# PortExpanderXRA1207.net
KiCad netlist of a schematic drawn in EAGLE
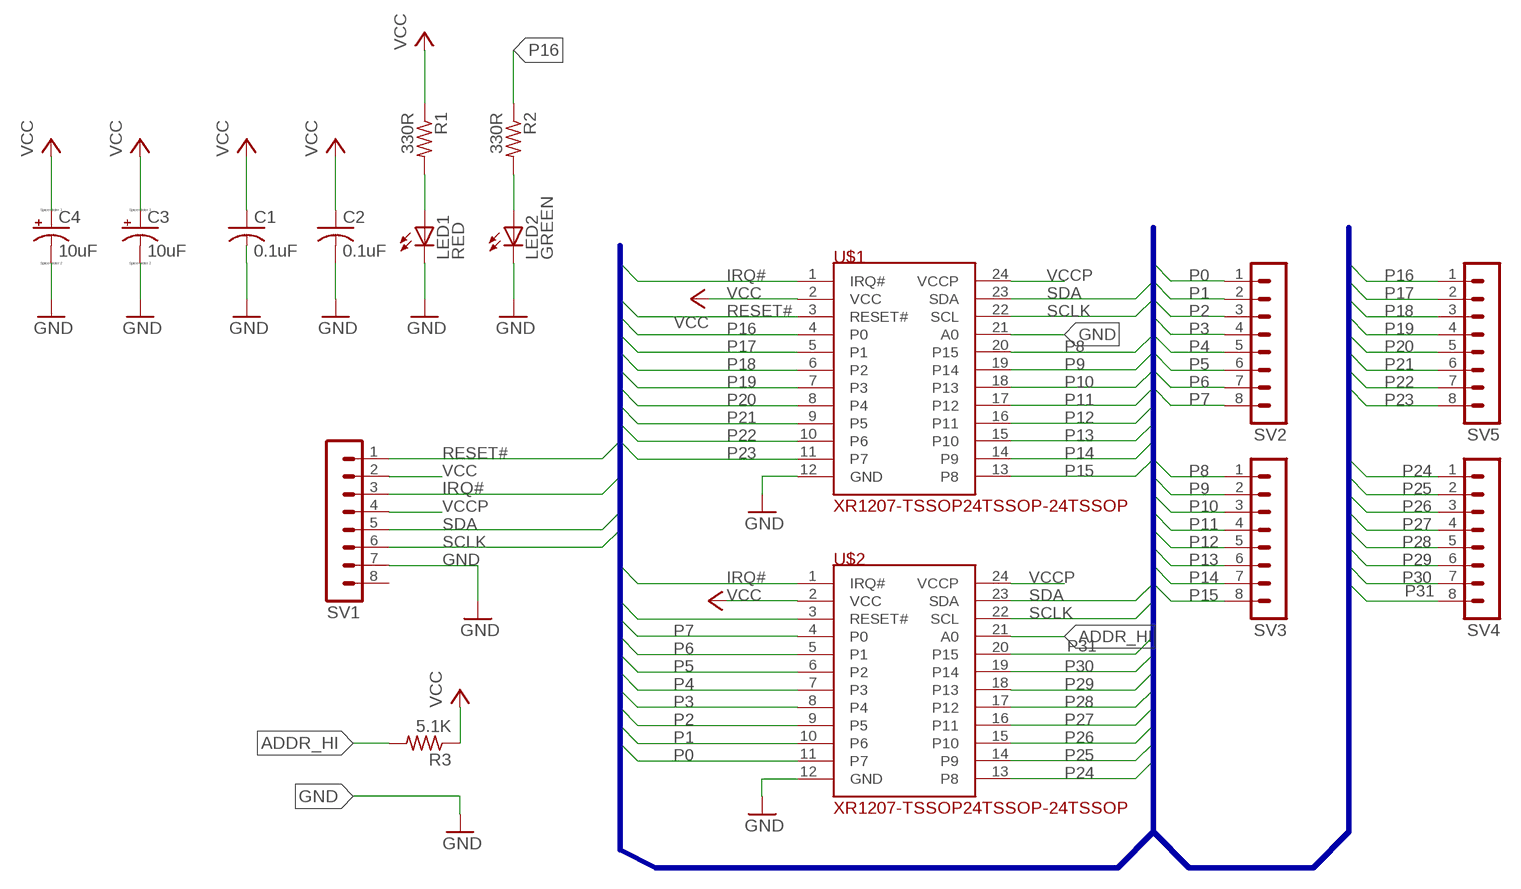
[diagram p0: schematic, sheet 1]

(export (version "E")
  (design (tool "Eeschema 10.0.6"))
  (components
    (comp (ref "C1")
      (value "0.1uF")
      (footprint "eagle-import:C1206")
      (libsource (lib "eagle-import") (part "C-USC1206"))
    )
    (comp (ref "C2")
      (value "0.1uF")
      (footprint "eagle-import:C1206")
      (libsource (lib "eagle-import") (part "C-USC1206"))
    )
    (comp (ref "C3")
      (value "10uF")
      (footprint "eagle-import:E5-5")
      (libsource (lib "eagle-import") (part "CPOL-USE5-5"))
    )
    (comp (ref "C4")
      (value "10uF")
      (footprint "eagle-import:E5-5")
      (libsource (lib "eagle-import") (part "CPOL-USE5-5"))
    )
    (comp (ref "LED1")
      (value "RED")
      (footprint "eagle-import:CHIPLED_0805")
      (libsource (lib "eagle-import") (part "LEDCHIPLED_0805"))
    )
    (comp (ref "LED2")
      (value "GREEN")
      (footprint "eagle-import:CHIPLED_0805")
      (libsource (lib "eagle-import") (part "LEDCHIPLED_0805"))
    )
    (comp (ref "R1")
      (value "330R")
      (footprint "eagle-import:R1206")
      (libsource (lib "eagle-import") (part "R-US_R1206"))
    )
    (comp (ref "R2")
      (value "330R")
      (footprint "eagle-import:R1206")
      (libsource (lib "eagle-import") (part "R-US_R1206"))
    )
    (comp (ref "R3")
      (value "5.1K")
      (footprint "eagle-import:R1206")
      (libsource (lib "eagle-import") (part "R-US_R1206"))
    )
    (comp (ref "SV1")
      (value "MA08-1")
      (footprint "eagle-import:MA08-1")
      (libsource (lib "eagle-import") (part "MA08-1"))
    )
    (comp (ref "SV2")
      (value "MA08-1")
      (footprint "eagle-import:MA08-1")
      (libsource (lib "eagle-import") (part "MA08-1"))
    )
    (comp (ref "SV3")
      (value "MA08-1")
      (footprint "eagle-import:MA08-1")
      (libsource (lib "eagle-import") (part "MA08-1"))
    )
    (comp (ref "SV4")
      (value "MA08-1")
      (footprint "eagle-import:MA08-1")
      (libsource (lib "eagle-import") (part "MA08-1"))
    )
    (comp (ref "SV5")
      (value "MA08-1")
      (footprint "eagle-import:MA08-1")
      (libsource (lib "eagle-import") (part "MA08-1"))
    )
    (comp (ref "U$1")
      (value "XR1207-TSSOP24TSSOP-24TSSOP")
      (footprint "eagle-import:TSSOP-24")
      (libsource (lib "eagle-import") (part "XR1207-TSSOP24TSSOPTSSOP-24"))
    )
    (comp (ref "U$2")
      (value "XR1207-TSSOP24TSSOP-24TSSOP")
      (footprint "eagle-import:TSSOP-24")
      (libsource (lib "eagle-import") (part "XR1207-TSSOP24TSSOPTSSOP-24"))
    )
  )
  (nets
    (net (code "1") (name "/IRQ#") (class "Default")
      (node (ref "SV1") (pin "3") (pinfunction "3_3") (pintype "passive"))
      (node (ref "U$1") (pin "1") (pinfunction "IRQ#_1") (pintype "bidirectional"))
      (node (ref "U$2") (pin "1") (pinfunction "IRQ#_1") (pintype "bidirectional"))
    )
    (net (code "2") (name "/P0") (class "Default")
      (node (ref "SV2") (pin "1") (pinfunction "1_1") (pintype "passive"))
      (node (ref "U$2") (pin "11") (pinfunction "P7_11") (pintype "bidirectional"))
    )
    (net (code "3") (name "/P1") (class "Default")
      (node (ref "SV2") (pin "2") (pinfunction "2_2") (pintype "passive"))
      (node (ref "U$2") (pin "10") (pinfunction "P6_10") (pintype "bidirectional"))
    )
    (net (code "4") (name "/P2") (class "Default")
      (node (ref "SV2") (pin "3") (pinfunction "3_3") (pintype "passive"))
      (node (ref "U$2") (pin "9") (pinfunction "P5_9") (pintype "bidirectional"))
    )
    (net (code "5") (name "/P3") (class "Default")
      (node (ref "SV2") (pin "4") (pinfunction "4_4") (pintype "passive"))
      (node (ref "U$2") (pin "8") (pinfunction "P4_8") (pintype "bidirectional"))
    )
    (net (code "6") (name "/P4") (class "Default")
      (node (ref "SV2") (pin "5") (pinfunction "5_5") (pintype "passive"))
      (node (ref "U$2") (pin "7") (pinfunction "P3_7") (pintype "bidirectional"))
    )
    (net (code "7") (name "/P5") (class "Default")
      (node (ref "SV2") (pin "6") (pinfunction "6_6") (pintype "passive"))
      (node (ref "U$2") (pin "6") (pinfunction "P2_6") (pintype "bidirectional"))
    )
    (net (code "8") (name "/P6") (class "Default")
      (node (ref "SV2") (pin "7") (pinfunction "7_7") (pintype "passive"))
      (node (ref "U$2") (pin "5") (pinfunction "P1_5") (pintype "bidirectional"))
    )
    (net (code "9") (name "/P7") (class "Default")
      (node (ref "SV2") (pin "8") (pinfunction "8_8") (pintype "passive"))
      (node (ref "U$2") (pin "4") (pinfunction "P0_4") (pintype "bidirectional"))
    )
    (net (code "10") (name "/P8") (class "Default")
      (node (ref "SV3") (pin "1") (pinfunction "1_1") (pintype "passive"))
      (node (ref "U$1") (pin "20") (pinfunction "P15_20") (pintype "bidirectional"))
    )
    (net (code "11") (name "/P9") (class "Default")
      (node (ref "SV3") (pin "2") (pinfunction "2_2") (pintype "passive"))
      (node (ref "U$1") (pin "19") (pinfunction "P14_19") (pintype "bidirectional"))
    )
    (net (code "12") (name "/P10") (class "Default")
      (node (ref "SV3") (pin "3") (pinfunction "3_3") (pintype "passive"))
      (node (ref "U$1") (pin "18") (pinfunction "P13_18") (pintype "bidirectional"))
    )
    (net (code "13") (name "/P11") (class "Default")
      (node (ref "SV3") (pin "4") (pinfunction "4_4") (pintype "passive"))
      (node (ref "U$1") (pin "17") (pinfunction "P12_17") (pintype "bidirectional"))
    )
    (net (code "14") (name "/P12") (class "Default")
      (node (ref "SV3") (pin "5") (pinfunction "5_5") (pintype "passive"))
      (node (ref "U$1") (pin "16") (pinfunction "P11_16") (pintype "bidirectional"))
    )
    (net (code "15") (name "/P13") (class "Default")
      (node (ref "SV3") (pin "6") (pinfunction "6_6") (pintype "passive"))
      (node (ref "U$1") (pin "15") (pinfunction "P10_15") (pintype "bidirectional"))
    )
    (net (code "16") (name "/P14") (class "Default")
      (node (ref "SV3") (pin "7") (pinfunction "7_7") (pintype "passive"))
      (node (ref "U$1") (pin "14") (pinfunction "P9_14") (pintype "bidirectional"))
    )
    (net (code "17") (name "/P15") (class "Default")
      (node (ref "SV3") (pin "8") (pinfunction "8_8") (pintype "passive"))
      (node (ref "U$1") (pin "13") (pinfunction "P8_13") (pintype "bidirectional"))
    )
    (net (code "18") (name "/P17") (class "Default")
      (node (ref "SV5") (pin "2") (pinfunction "2_2") (pintype "passive"))
      (node (ref "U$1") (pin "5") (pinfunction "P1_5") (pintype "bidirectional"))
    )
    (net (code "19") (name "/P18") (class "Default")
      (node (ref "SV5") (pin "3") (pinfunction "3_3") (pintype "passive"))
      (node (ref "U$1") (pin "6") (pinfunction "P2_6") (pintype "bidirectional"))
    )
    (net (code "20") (name "/P19") (class "Default")
      (node (ref "SV5") (pin "4") (pinfunction "4_4") (pintype "passive"))
      (node (ref "U$1") (pin "7") (pinfunction "P3_7") (pintype "bidirectional"))
    )
    (net (code "21") (name "/P20") (class "Default")
      (node (ref "SV5") (pin "5") (pinfunction "5_5") (pintype "passive"))
      (node (ref "U$1") (pin "8") (pinfunction "P4_8") (pintype "bidirectional"))
    )
    (net (code "22") (name "/P21") (class "Default")
      (node (ref "SV5") (pin "6") (pinfunction "6_6") (pintype "passive"))
      (node (ref "U$1") (pin "9") (pinfunction "P5_9") (pintype "bidirectional"))
    )
    (net (code "23") (name "/P22") (class "Default")
      (node (ref "SV5") (pin "7") (pinfunction "7_7") (pintype "passive"))
      (node (ref "U$1") (pin "10") (pinfunction "P6_10") (pintype "bidirectional"))
    )
    (net (code "24") (name "/P23") (class "Default")
      (node (ref "SV5") (pin "8") (pinfunction "8_8") (pintype "passive"))
      (node (ref "U$1") (pin "11") (pinfunction "P7_11") (pintype "bidirectional"))
    )
    (net (code "25") (name "/P24") (class "Default")
      (node (ref "SV4") (pin "1") (pinfunction "1_1") (pintype "passive"))
      (node (ref "U$2") (pin "13") (pinfunction "P8_13") (pintype "bidirectional"))
    )
    (net (code "26") (name "/P25") (class "Default")
      (node (ref "SV4") (pin "2") (pinfunction "2_2") (pintype "passive"))
      (node (ref "U$2") (pin "14") (pinfunction "P9_14") (pintype "bidirectional"))
    )
    (net (code "27") (name "/P26") (class "Default")
      (node (ref "SV4") (pin "3") (pinfunction "3_3") (pintype "passive"))
      (node (ref "U$2") (pin "15") (pinfunction "P10_15") (pintype "bidirectional"))
    )
    (net (code "28") (name "/P27") (class "Default")
      (node (ref "SV4") (pin "4") (pinfunction "4_4") (pintype "passive"))
      (node (ref "U$2") (pin "16") (pinfunction "P11_16") (pintype "bidirectional"))
    )
    (net (code "29") (name "/P28") (class "Default")
      (node (ref "SV4") (pin "5") (pinfunction "5_5") (pintype "passive"))
      (node (ref "U$2") (pin "17") (pinfunction "P12_17") (pintype "bidirectional"))
    )
    (net (code "30") (name "/P29") (class "Default")
      (node (ref "SV4") (pin "6") (pinfunction "6_6") (pintype "passive"))
      (node (ref "U$2") (pin "18") (pinfunction "P13_18") (pintype "bidirectional"))
    )
    (net (code "31") (name "/P30") (class "Default")
      (node (ref "SV4") (pin "7") (pinfunction "7_7") (pintype "passive"))
      (node (ref "U$2") (pin "19") (pinfunction "P14_19") (pintype "bidirectional"))
    )
    (net (code "32") (name "/P31") (class "Default")
      (node (ref "SV4") (pin "8") (pinfunction "8_8") (pintype "passive"))
      (node (ref "U$2") (pin "20") (pinfunction "P15_20") (pintype "bidirectional"))
    )
    (net (code "33") (name "/RESET#") (class "Default")
      (node (ref "SV1") (pin "1") (pinfunction "1_1") (pintype "passive"))
      (node (ref "U$1") (pin "3") (pinfunction "RESET#_3") (pintype "bidirectional"))
      (node (ref "U$2") (pin "3") (pinfunction "RESET#_3") (pintype "bidirectional"))
    )
    (net (code "34") (name "/SCLK") (class "Default")
      (node (ref "SV1") (pin "6") (pinfunction "6_6") (pintype "passive"))
      (node (ref "U$1") (pin "22") (pinfunction "SCL_22") (pintype "bidirectional"))
      (node (ref "U$2") (pin "22") (pinfunction "SCL_22") (pintype "bidirectional"))
    )
    (net (code "35") (name "/SDA") (class "Default")
      (node (ref "SV1") (pin "5") (pinfunction "5_5") (pintype "passive"))
      (node (ref "U$1") (pin "23") (pinfunction "SDA_23") (pintype "bidirectional"))
      (node (ref "U$2") (pin "23") (pinfunction "SDA_23") (pintype "bidirectional"))
    )
    (net (code "36") (name "/VCCP") (class "Default")
      (node (ref "SV1") (pin "4") (pinfunction "4_4") (pintype "passive"))
      (node (ref "U$1") (pin "24") (pinfunction "VCCP_24") (pintype "bidirectional"))
      (node (ref "U$2") (pin "24") (pinfunction "VCCP_24") (pintype "bidirectional"))
    )
    (net (code "37") (name "ADDR_HI") (class "Default")
      (node (ref "R3") (pin "2") (pinfunction "2_2") (pintype "passive"))
      (node (ref "U$2") (pin "21") (pinfunction "A0_21") (pintype "bidirectional"))
    )
    (net (code "38") (name "GND") (class "Default")
      (node (ref "C1") (pin "2") (pinfunction "2_2") (pintype "passive"))
      (node (ref "C2") (pin "2") (pinfunction "2_2") (pintype "passive"))
      (node (ref "C3") (pin "-") (pinfunction "-_-") (pintype "passive"))
      (node (ref "C4") (pin "-") (pinfunction "-_-") (pintype "passive"))
      (node (ref "LED1") (pin "C") (pinfunction "C_C") (pintype "passive"))
      (node (ref "LED2") (pin "C") (pinfunction "C_C") (pintype "passive"))
      (node (ref "SV1") (pin "7") (pinfunction "7_7") (pintype "passive"))
      (node (ref "U$1") (pin "12") (pinfunction "GND_12") (pintype "bidirectional"))
      (node (ref "U$1") (pin "21") (pinfunction "A0_21") (pintype "bidirectional"))
      (node (ref "U$2") (pin "12") (pinfunction "GND_12") (pintype "bidirectional"))
    )
    (net (code "39") (name "Net-(LED1-PadA)") (class "Default")
      (node (ref "LED1") (pin "A") (pinfunction "A_A") (pintype "passive"))
      (node (ref "R1") (pin "2") (pinfunction "2_2") (pintype "passive"))
    )
    (net (code "40") (name "Net-(LED2-PadA)") (class "Default")
      (node (ref "LED2") (pin "A") (pinfunction "A_A") (pintype "passive"))
      (node (ref "R2") (pin "2") (pinfunction "2_2") (pintype "passive"))
    )
    (net (code "41") (name "P16") (class "Default")
      (node (ref "R2") (pin "1") (pinfunction "1_1") (pintype "passive"))
      (node (ref "SV5") (pin "1") (pinfunction "1_1") (pintype "passive"))
      (node (ref "U$1") (pin "4") (pinfunction "P0_4") (pintype "bidirectional"))
    )
    (net (code "42") (name "VCC") (class "Default")
      (node (ref "C1") (pin "1") (pinfunction "1_1") (pintype "passive"))
      (node (ref "C2") (pin "1") (pinfunction "1_1") (pintype "passive"))
      (node (ref "C3") (pin "+") (pinfunction "+_+") (pintype "passive"))
      (node (ref "C4") (pin "+") (pinfunction "+_+") (pintype "passive"))
      (node (ref "R1") (pin "1") (pinfunction "1_1") (pintype "passive"))
      (node (ref "R3") (pin "1") (pinfunction "1_1") (pintype "passive"))
      (node (ref "SV1") (pin "2") (pinfunction "2_2") (pintype "passive"))
      (node (ref "U$1") (pin "2") (pinfunction "VCC_2") (pintype "bidirectional"))
      (node (ref "U$2") (pin "2") (pinfunction "VCC_2") (pintype "bidirectional"))
    )
    (net (code "43") (name "unconnected-(SV1-Pad8)") (class "Default")
      (node (ref "SV1") (pin "8") (pinfunction "8_8") (pintype "passive"))
    )
  )
)
